# STM32F103ZE.net
KiCad netlist of a schematic drawn in Altium Designer
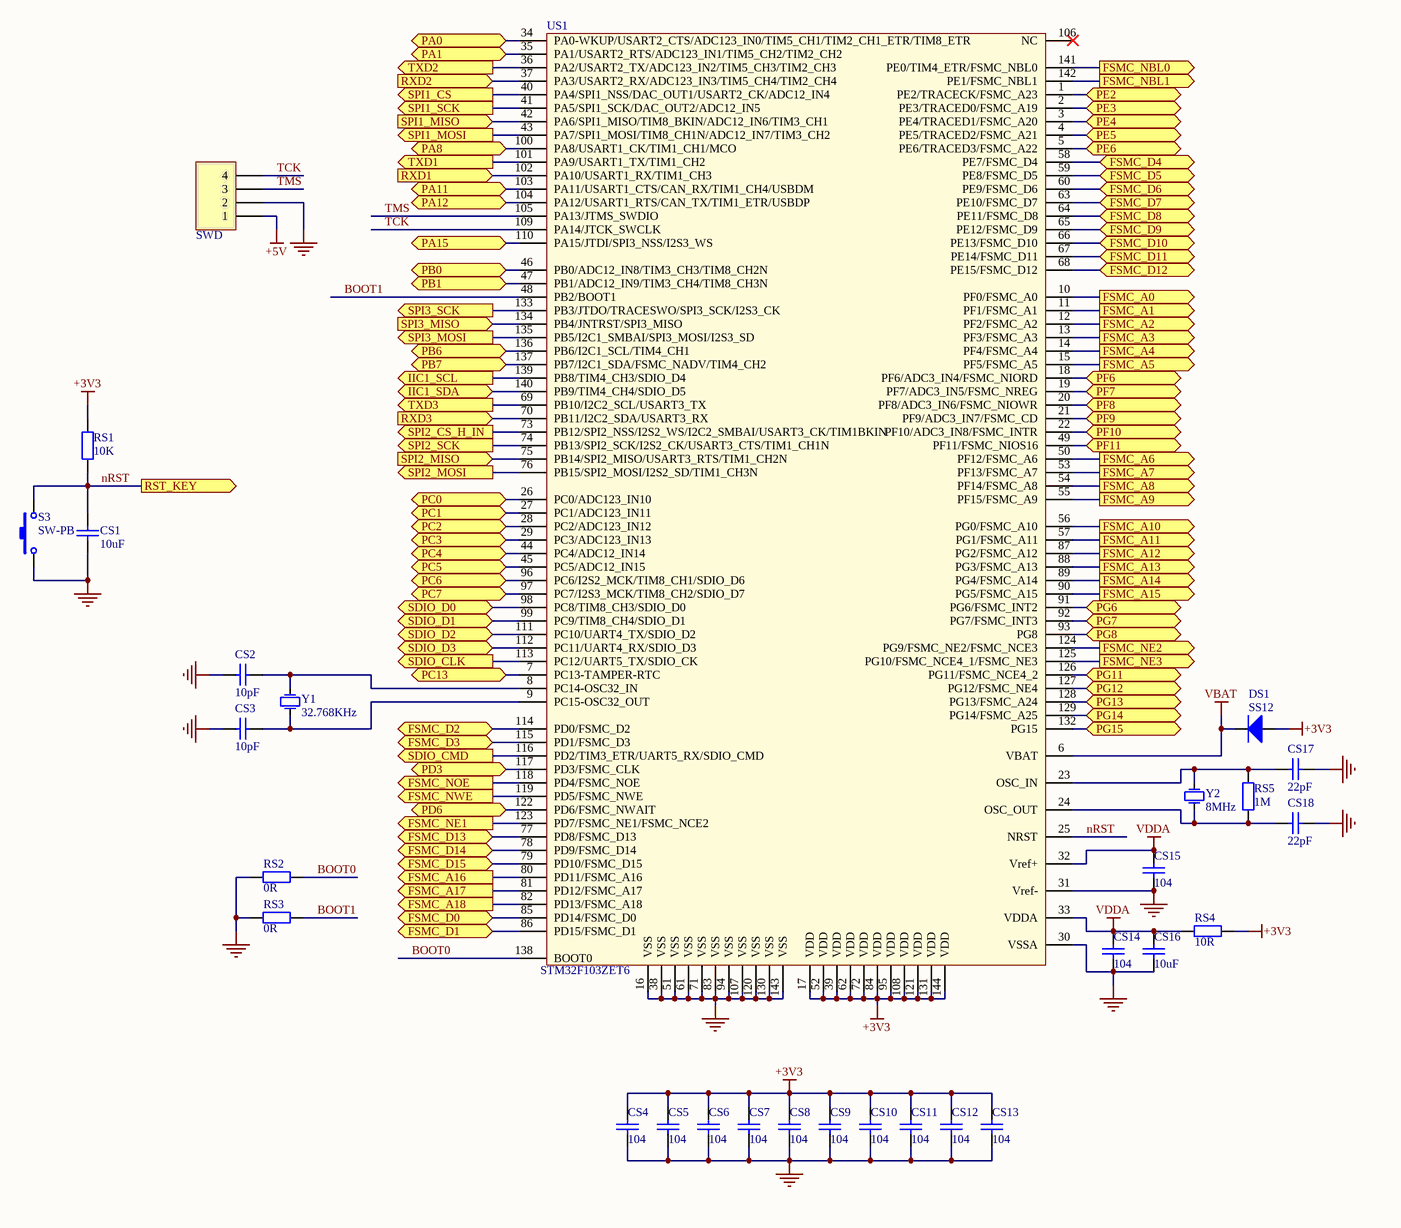
[diagram p0: STM32F103ZE.SchDoc]

(export (version "E")
  (design (tool "Eeschema 10.0.6"))
  (components
    (comp (ref "CS1")
      (value "10uF")
      (footprint "CAPC1608N")
      (description "Capacitor")
      (fields (field (name "Comment") "Cap1") (field (name "PUBLISHER") "Altium Limited"))
      (libsource (lib "Peace的集成库") (part "Cap1"))
    )
    (comp (ref "CS2")
      (value "10pF")
      (footprint "CAPC1608N")
      (description "Capacitor")
      (fields (field (name "Comment") "Cap1") (field (name "PUBLISHER") "Altium Limited"))
      (libsource (lib "Peace的集成库") (part "Cap1"))
    )
    (comp (ref "CS3")
      (value "10pF")
      (footprint "CAPC1608N")
      (description "Capacitor")
      (fields (field (name "Comment") "Cap1") (field (name "PUBLISHER") "Altium Limited"))
      (libsource (lib "Peace的集成库") (part "Cap1"))
    )
    (comp (ref "CS4")
      (value "104")
      (footprint "CAPC1608N")
      (description "Capacitor")
      (fields (field (name "Comment") "Cap1") (field (name "PUBLISHER") "Altium Limited"))
      (libsource (lib "Peace的集成库") (part "Cap1"))
    )
    (comp (ref "CS5")
      (value "104")
      (footprint "CAPC1608N")
      (description "Capacitor")
      (fields (field (name "Comment") "Cap1") (field (name "PUBLISHER") "Altium Limited"))
      (libsource (lib "Peace的集成库") (part "Cap1"))
    )
    (comp (ref "CS6")
      (value "104")
      (footprint "CAPC1608N")
      (description "Capacitor")
      (fields (field (name "Comment") "Cap1") (field (name "PUBLISHER") "Altium Limited"))
      (libsource (lib "Peace的集成库") (part "Cap1"))
    )
    (comp (ref "CS7")
      (value "104")
      (footprint "CAPC1608N")
      (description "Capacitor")
      (fields (field (name "Comment") "Cap1") (field (name "PUBLISHER") "Altium Limited"))
      (libsource (lib "Peace的集成库") (part "Cap1"))
    )
    (comp (ref "CS8")
      (value "104")
      (footprint "CAPC1608N")
      (description "Capacitor")
      (fields (field (name "Comment") "Cap1") (field (name "PUBLISHER") "Altium Limited"))
      (libsource (lib "Peace的集成库") (part "Cap1"))
    )
    (comp (ref "CS9")
      (value "104")
      (footprint "CAPC1608N")
      (description "Capacitor")
      (fields (field (name "Comment") "Cap1") (field (name "PUBLISHER") "Altium Limited"))
      (libsource (lib "Peace的集成库") (part "Cap1"))
    )
    (comp (ref "CS10")
      (value "104")
      (footprint "CAPC1608N")
      (description "Capacitor")
      (fields (field (name "Comment") "Cap1") (field (name "PUBLISHER") "Altium Limited"))
      (libsource (lib "Peace的集成库") (part "Cap1"))
    )
    (comp (ref "CS11")
      (value "104")
      (footprint "CAPC1608N")
      (description "Capacitor")
      (fields (field (name "Comment") "Cap1") (field (name "PUBLISHER") "Altium Limited"))
      (libsource (lib "Peace的集成库") (part "Cap1"))
    )
    (comp (ref "CS12")
      (value "104")
      (footprint "CAPC1608N")
      (description "Capacitor")
      (fields (field (name "Comment") "Cap1") (field (name "PUBLISHER") "Altium Limited"))
      (libsource (lib "Peace的集成库") (part "Cap1"))
    )
    (comp (ref "CS13")
      (value "104")
      (footprint "CAPC1608N")
      (description "Capacitor")
      (fields (field (name "Comment") "Cap1") (field (name "PUBLISHER") "Altium Limited"))
      (libsource (lib "Peace的集成库") (part "Cap1"))
    )
    (comp (ref "CS14")
      (value "104")
      (footprint "CAPC1608N")
      (description "Capacitor")
      (fields (field (name "Comment") "Cap1") (field (name "PUBLISHER") "Altium Limited"))
      (libsource (lib "Peace的集成库") (part "Cap1"))
    )
    (comp (ref "CS15")
      (value "104")
      (footprint "CAPC1608N")
      (description "Capacitor")
      (fields (field (name "Comment") "Cap1") (field (name "PUBLISHER") "Altium Limited"))
      (libsource (lib "Peace的集成库") (part "Cap1"))
    )
    (comp (ref "CS16")
      (value "10uF")
      (footprint "CAPC1608N")
      (description "Capacitor")
      (fields (field (name "Comment") "Cap1") (field (name "PUBLISHER") "Altium Limited"))
      (libsource (lib "Peace的集成库") (part "Cap1"))
    )
    (comp (ref "CS17")
      (value "22pF")
      (footprint "CAPC1608N")
      (description "Capacitor")
      (fields (field (name "Comment") "Cap1") (field (name "PUBLISHER") "Altium Limited"))
      (libsource (lib "Peace的集成库") (part "Cap1"))
    )
    (comp (ref "CS18")
      (value "22pF")
      (footprint "CAPC1608N")
      (description "Capacitor")
      (fields (field (name "Comment") "Cap1") (field (name "PUBLISHER") "Altium Limited"))
      (libsource (lib "Peace的集成库") (part "Cap1"))
    )
    (comp (ref "DS1")
      (value "Diode")
      (footprint "DO-214AC")
      (fields (field (name "SMA") "SS12"))
      (libsource (lib "Peace的集成库") (part "Diode"))
    )
    (comp (ref "RS1")
      (value "10K")
      (footprint "RESC1608N")
      (description "Resistor")
      (fields (field (name "Comment") "Res1") (field (name "PUBLISHER") "Altium Limited"))
      (libsource (lib "Peace的集成库") (part "Res1"))
    )
    (comp (ref "RS2")
      (value "0R")
      (footprint "RESC1608N")
      (description "Resistor")
      (fields (field (name "Comment") "Res1") (field (name "PUBLISHER") "Altium Limited"))
      (libsource (lib "") (part "Res1_1"))
    )
    (comp (ref "RS3")
      (value "0R")
      (footprint "RESC1608N")
      (description "Resistor")
      (fields (field (name "Comment") "Res1") (field (name "PUBLISHER") "Altium Limited"))
      (libsource (lib "") (part "Res1_1"))
    )
    (comp (ref "RS4")
      (value "10R")
      (footprint "RESC1608N")
      (description "Resistor")
      (fields (field (name "Comment") "Res1") (field (name "PUBLISHER") "Altium Limited"))
      (libsource (lib "") (part "Res1_1"))
    )
    (comp (ref "RS5")
      (value "1M")
      (footprint "RESC1608N")
      (description "Resistor")
      (fields (field (name "Comment") "Res1") (field (name "PUBLISHER") "Altium Limited"))
      (libsource (lib "Peace的集成库") (part "Res1"))
    )
    (comp (ref "S3")
      (value "SW-PB")
      (footprint "SW-3x6")
      (description "Switch")
      (fields (field (name "PUBLISHER") "Altium Limited"))
      (libsource (lib "Peace的集成库") (part "SW-PB"))
    )
    (comp (ref "SWD")
      (value "Header 4")
      (footprint "HDR1X4")
      (description "Header, 4-Pin")
      (fields (field (name "PUBLISHER") "Altium Limited"))
      (libsource (lib "Peace的集成库") (part "Header 4"))
    )
    (comp (ref "US1")
      (value "STM32F103ZET6")
      (footprint "LQFP144")
      (libsource (lib "Peace的集成库") (part "STM32F103ZET6"))
    )
    (comp (ref "Y1")
      (value "32.768KHz")
      (footprint "XTAL-206")
      (description "Crystal Oscillator")
      (fields (field (name "PUBLISHER") "Altium Limited"))
      (libsource (lib "Peace的集成库") (part "XTAL"))
    )
    (comp (ref "Y2")
      (value "8MHz")
      (footprint "49S")
      (description "Crystal Oscillator")
      (fields (field (name "PUBLISHER") "Altium Limited"))
      (libsource (lib "Peace的集成库") (part "XTAL"))
    )
  )
  (nets
    (net (code "1") (name "+3V3") (class "Default")
      (node (ref "CS10") (pin "2") (pinfunction "2_2") (pintype "passive"))
      (node (ref "CS11") (pin "2") (pinfunction "2_2") (pintype "passive"))
      (node (ref "CS12") (pin "2") (pinfunction "2_2") (pintype "passive"))
      (node (ref "CS13") (pin "2") (pinfunction "2_2") (pintype "passive"))
      (node (ref "CS4") (pin "2") (pinfunction "2_2") (pintype "passive"))
      (node (ref "CS5") (pin "2") (pinfunction "2_2") (pintype "passive"))
      (node (ref "CS6") (pin "2") (pinfunction "2_2") (pintype "passive"))
      (node (ref "CS7") (pin "2") (pinfunction "2_2") (pintype "passive"))
      (node (ref "CS8") (pin "2") (pinfunction "2_2") (pintype "passive"))
      (node (ref "CS9") (pin "2") (pinfunction "2_2") (pintype "passive"))
      (node (ref "DS1") (pin "1") (pinfunction "A_1") (pintype "passive"))
      (node (ref "RS1") (pin "2") (pinfunction "2_2") (pintype "passive"))
      (node (ref "RS4") (pin "2") (pinfunction "2_2") (pintype "passive"))
      (node (ref "US1") (pin "108") (pinfunction "VDD_108") (pintype "passive"))
      (node (ref "US1") (pin "121") (pinfunction "VDD_121") (pintype "passive"))
      (node (ref "US1") (pin "131") (pinfunction "VDD_131") (pintype "passive"))
      (node (ref "US1") (pin "144") (pinfunction "VDD_144") (pintype "passive"))
      (node (ref "US1") (pin "17") (pinfunction "VDD_17") (pintype "passive"))
      (node (ref "US1") (pin "39") (pinfunction "VDD_39") (pintype "passive"))
      (node (ref "US1") (pin "52") (pinfunction "VDD_52") (pintype "passive"))
      (node (ref "US1") (pin "62") (pinfunction "VDD_62") (pintype "passive"))
      (node (ref "US1") (pin "72") (pinfunction "VDD_72") (pintype "passive"))
      (node (ref "US1") (pin "84") (pinfunction "VDD_84") (pintype "passive"))
      (node (ref "US1") (pin "95") (pinfunction "VDD_95") (pintype "passive"))
    )
    (net (code "2") (name "+5V") (class "Default")
      (node (ref "SWD") (pin "1") (pinfunction "1_1") (pintype "passive"))
    )
    (net (code "3") (name "/BOOT0") (class "Default")
      (node (ref "RS2") (pin "2") (pinfunction "2_2") (pintype "passive"))
      (node (ref "US1") (pin "138") (pinfunction "BOOT0_138") (pintype "passive"))
    )
    (net (code "4") (name "/BOOT1") (class "Default")
      (node (ref "RS3") (pin "2") (pinfunction "2_2") (pintype "passive"))
      (node (ref "US1") (pin "48") (pinfunction "PB2/BOOT1_48") (pintype "passive"))
    )
    (net (code "5") (name "/FSMC_A0") (class "Default")
      (node (ref "US1") (pin "10") (pinfunction "PF0/FSMC_A0_10") (pintype "passive"))
    )
    (net (code "6") (name "/FSMC_A1") (class "Default")
      (node (ref "US1") (pin "11") (pinfunction "PF1/FSMC_A1_11") (pintype "passive"))
    )
    (net (code "7") (name "/FSMC_A2") (class "Default")
      (node (ref "US1") (pin "12") (pinfunction "PF2/FSMC_A2_12") (pintype "passive"))
    )
    (net (code "8") (name "/FSMC_A3") (class "Default")
      (node (ref "US1") (pin "13") (pinfunction "PF3/FSMC_A3_13") (pintype "passive"))
    )
    (net (code "9") (name "/FSMC_A4") (class "Default")
      (node (ref "US1") (pin "14") (pinfunction "PF4/FSMC_A4_14") (pintype "passive"))
    )
    (net (code "10") (name "/FSMC_A5") (class "Default")
      (node (ref "US1") (pin "15") (pinfunction "PF5/FSMC_A5_15") (pintype "passive"))
    )
    (net (code "11") (name "/FSMC_A6") (class "Default")
      (node (ref "US1") (pin "50") (pinfunction "PF12/FSMC_A6_50") (pintype "passive"))
    )
    (net (code "12") (name "/FSMC_A7") (class "Default")
      (node (ref "US1") (pin "53") (pinfunction "PF13/FSMC_A7_53") (pintype "passive"))
    )
    (net (code "13") (name "/FSMC_A8") (class "Default")
      (node (ref "US1") (pin "54") (pinfunction "PF14/FSMC_A8_54") (pintype "passive"))
    )
    (net (code "14") (name "/FSMC_A9") (class "Default")
      (node (ref "US1") (pin "55") (pinfunction "PF15/FSMC_A9_55") (pintype "passive"))
    )
    (net (code "15") (name "/FSMC_A10") (class "Default")
      (node (ref "US1") (pin "56") (pinfunction "PG0/FSMC_A10_56") (pintype "passive"))
    )
    (net (code "16") (name "/FSMC_A11") (class "Default")
      (node (ref "US1") (pin "57") (pinfunction "PG1/FSMC_A11_57") (pintype "passive"))
    )
    (net (code "17") (name "/FSMC_A12") (class "Default")
      (node (ref "US1") (pin "87") (pinfunction "PG2/FSMC_A12_87") (pintype "passive"))
    )
    (net (code "18") (name "/FSMC_A13") (class "Default")
      (node (ref "US1") (pin "88") (pinfunction "PG3/FSMC_A13_88") (pintype "passive"))
    )
    (net (code "19") (name "/FSMC_A14") (class "Default")
      (node (ref "US1") (pin "89") (pinfunction "PG4/FSMC_A14_89") (pintype "passive"))
    )
    (net (code "20") (name "/FSMC_A15") (class "Default")
      (node (ref "US1") (pin "90") (pinfunction "PG5/FSMC_A15_90") (pintype "passive"))
    )
    (net (code "21") (name "/FSMC_A16") (class "Default")
      (node (ref "US1") (pin "80") (pinfunction "PD11/FSMC_A16_80") (pintype "passive"))
    )
    (net (code "22") (name "/FSMC_A17") (class "Default")
      (node (ref "US1") (pin "81") (pinfunction "PD12/FSMC_A17_81") (pintype "passive"))
    )
    (net (code "23") (name "/FSMC_A18") (class "Default")
      (node (ref "US1") (pin "82") (pinfunction "PD13/FSMC_A18_82") (pintype "passive"))
    )
    (net (code "24") (name "/FSMC_D0") (class "Default")
      (node (ref "US1") (pin "85") (pinfunction "PD14/FSMC_D0_85") (pintype "passive"))
    )
    (net (code "25") (name "/FSMC_D1") (class "Default")
      (node (ref "US1") (pin "86") (pinfunction "PD15/FSMC_D1_86") (pintype "passive"))
    )
    (net (code "26") (name "/FSMC_D2") (class "Default")
      (node (ref "US1") (pin "114") (pinfunction "PD0/FSMC_D2_114") (pintype "passive"))
    )
    (net (code "27") (name "/FSMC_D3") (class "Default")
      (node (ref "US1") (pin "115") (pinfunction "PD1/FSMC_D3_115") (pintype "passive"))
    )
    (net (code "28") (name "/FSMC_D4") (class "Default")
      (node (ref "US1") (pin "58") (pinfunction "PE7/FSMC_D4_58") (pintype "passive"))
    )
    (net (code "29") (name "/FSMC_D5") (class "Default")
      (node (ref "US1") (pin "59") (pinfunction "PE8/FSMC_D5_59") (pintype "passive"))
    )
    (net (code "30") (name "/FSMC_D6") (class "Default")
      (node (ref "US1") (pin "60") (pinfunction "PE9/FSMC_D6_60") (pintype "passive"))
    )
    (net (code "31") (name "/FSMC_D7") (class "Default")
      (node (ref "US1") (pin "63") (pinfunction "PE10/FSMC_D7_63") (pintype "passive"))
    )
    (net (code "32") (name "/FSMC_D8") (class "Default")
      (node (ref "US1") (pin "64") (pinfunction "PE11/FSMC_D8_64") (pintype "passive"))
    )
    (net (code "33") (name "/FSMC_D9") (class "Default")
      (node (ref "US1") (pin "65") (pinfunction "PE12/FSMC_D9_65") (pintype "passive"))
    )
    (net (code "34") (name "/FSMC_D10") (class "Default")
      (node (ref "US1") (pin "66") (pinfunction "PE13/FSMC_D10_66") (pintype "passive"))
    )
    (net (code "35") (name "/FSMC_D11") (class "Default")
      (node (ref "US1") (pin "67") (pinfunction "PE14/FSMC_D11_67") (pintype "passive"))
    )
    (net (code "36") (name "/FSMC_D12") (class "Default")
      (node (ref "US1") (pin "68") (pinfunction "PE15/FSMC_D12_68") (pintype "passive"))
    )
    (net (code "37") (name "/FSMC_D13") (class "Default")
      (node (ref "US1") (pin "77") (pinfunction "PD8/FSMC_D13_77") (pintype "passive"))
    )
    (net (code "38") (name "/FSMC_D14") (class "Default")
      (node (ref "US1") (pin "78") (pinfunction "PD9/FSMC_D14_78") (pintype "passive"))
    )
    (net (code "39") (name "/FSMC_D15") (class "Default")
      (node (ref "US1") (pin "79") (pinfunction "PD10/FSMC_D15_79") (pintype "passive"))
    )
    (net (code "40") (name "/FSMC_NBL0") (class "Default")
      (node (ref "US1") (pin "141") (pinfunction "PE0/TIM4_ETR/FSMC_NBL0_141") (pintype "passive"))
    )
    (net (code "41") (name "/FSMC_NBL1") (class "Default")
      (node (ref "US1") (pin "142") (pinfunction "PE1/FSMC_NBL1_142") (pintype "passive"))
    )
    (net (code "42") (name "/FSMC_NE1") (class "Default")
      (node (ref "US1") (pin "123") (pinfunction "PD7/FSMC_NE1/FSMC_NCE2_123") (pintype "passive"))
    )
    (net (code "43") (name "/FSMC_NE2") (class "Default")
      (node (ref "US1") (pin "124") (pinfunction "PG9/FSMC_NE2/FSMC_NCE3_124") (pintype "passive"))
    )
    (net (code "44") (name "/FSMC_NE3") (class "Default")
      (node (ref "US1") (pin "125") (pinfunction "PG10/FSMC_NCE4_1/FSMC_NE3_125") (pintype "passive"))
    )
    (net (code "45") (name "/FSMC_NOE") (class "Default")
      (node (ref "US1") (pin "118") (pinfunction "PD4/FSMC_NOE_118") (pintype "passive"))
    )
    (net (code "46") (name "/FSMC_NWE") (class "Default")
      (node (ref "US1") (pin "119") (pinfunction "PD5/FSMC_NWE_119") (pintype "passive"))
    )
    (net (code "47") (name "/IIC1_SCL") (class "Default")
      (node (ref "US1") (pin "139") (pinfunction "PB8/TIM4_CH3/SDIO_D4_139") (pintype "passive"))
    )
    (net (code "48") (name "/IIC1_SDA") (class "Default")
      (node (ref "US1") (pin "140") (pinfunction "PB9/TIM4_CH4/SDIO_D5_140") (pintype "passive"))
    )
    (net (code "49") (name "/PA0") (class "Default")
      (node (ref "US1") (pin "34") (pinfunction "PA0-WKUP/USART2_CTS/ADC123_IN0/TIM5_CH1/TIM2_CH1_ETR/TIM8_ETR_34") (pintype "passive"))
    )
    (net (code "50") (name "/PA1") (class "Default")
      (node (ref "US1") (pin "35") (pinfunction "PA1/USART2_RTS/ADC123_IN1/TIM5_CH2/TIM2_CH2_35") (pintype "passive"))
    )
    (net (code "51") (name "/PA8") (class "Default")
      (node (ref "US1") (pin "100") (pinfunction "PA8/USART1_CK/TIM1_CH1/MCO_100") (pintype "passive"))
    )
    (net (code "52") (name "/PA11") (class "Default")
      (node (ref "US1") (pin "103") (pinfunction "PA11/USART1_CTS/CAN_RX/TIM1_CH4/USBDM_103") (pintype "passive"))
    )
    (net (code "53") (name "/PA12") (class "Default")
      (node (ref "US1") (pin "104") (pinfunction "PA12/USART1_RTS/CAN_TX/TIM1_ETR/USBDP_104") (pintype "passive"))
    )
    (net (code "54") (name "/PA15") (class "Default")
      (node (ref "US1") (pin "110") (pinfunction "PA15/JTDI/SPI3_NSS/I2S3_WS_110") (pintype "passive"))
    )
    (net (code "55") (name "/PB0") (class "Default")
      (node (ref "US1") (pin "46") (pinfunction "PB0/ADC12_IN8/TIM3_CH3/TIM8_CH2N_46") (pintype "passive"))
    )
    (net (code "56") (name "/PB1") (class "Default")
      (node (ref "US1") (pin "47") (pinfunction "PB1/ADC12_IN9/TIM3_CH4/TIM8_CH3N_47") (pintype "passive"))
    )
    (net (code "57") (name "/PB6") (class "Default")
      (node (ref "US1") (pin "136") (pinfunction "PB6/I2C1_SCL/TIM4_CH1_136") (pintype "passive"))
    )
    (net (code "58") (name "/PB7") (class "Default")
      (node (ref "US1") (pin "137") (pinfunction "PB7/I2C1_SDA/FSMC_NADV/TIM4_CH2_137") (pintype "passive"))
    )
    (net (code "59") (name "/PC0") (class "Default")
      (node (ref "US1") (pin "26") (pinfunction "PC0/ADC123_IN10_26") (pintype "passive"))
    )
    (net (code "60") (name "/PC1") (class "Default")
      (node (ref "US1") (pin "27") (pinfunction "PC1/ADC123_IN11_27") (pintype "passive"))
    )
    (net (code "61") (name "/PC2") (class "Default")
      (node (ref "US1") (pin "28") (pinfunction "PC2/ADC123_IN12_28") (pintype "passive"))
    )
    (net (code "62") (name "/PC3") (class "Default")
      (node (ref "US1") (pin "29") (pinfunction "PC3/ADC123_IN13_29") (pintype "passive"))
    )
    (net (code "63") (name "/PC4") (class "Default")
      (node (ref "US1") (pin "44") (pinfunction "PC4/ADC12_IN14_44") (pintype "passive"))
    )
    (net (code "64") (name "/PC5") (class "Default")
      (node (ref "US1") (pin "45") (pinfunction "PC5/ADC12_IN15_45") (pintype "passive"))
    )
    (net (code "65") (name "/PC6") (class "Default")
      (node (ref "US1") (pin "96") (pinfunction "PC6/I2S2_MCK/TIM8_CH1/SDIO_D6_96") (pintype "passive"))
    )
    (net (code "66") (name "/PC7") (class "Default")
      (node (ref "US1") (pin "97") (pinfunction "PC7/I2S3_MCK/TIM8_CH2/SDIO_D7_97") (pintype "passive"))
    )
    (net (code "67") (name "/PC13") (class "Default")
      (node (ref "US1") (pin "7") (pinfunction "PC13-TAMPER-RTC_7") (pintype "passive"))
    )
    (net (code "68") (name "/PD3") (class "Default")
      (node (ref "US1") (pin "117") (pinfunction "PD3/FSMC_CLK_117") (pintype "passive"))
    )
    (net (code "69") (name "/PD6") (class "Default")
      (node (ref "US1") (pin "122") (pinfunction "PD6/FSMC_NWAIT_122") (pintype "passive"))
    )
    (net (code "70") (name "/PE2") (class "Default")
      (node (ref "US1") (pin "1") (pinfunction "PE2/TRACECK/FSMC_A23_1") (pintype "passive"))
    )
    (net (code "71") (name "/PE3") (class "Default")
      (node (ref "US1") (pin "2") (pinfunction "PE3/TRACED0/FSMC_A19_2") (pintype "passive"))
    )
    (net (code "72") (name "/PE4") (class "Default")
      (node (ref "US1") (pin "3") (pinfunction "PE4/TRACED1/FSMC_A20_3") (pintype "passive"))
    )
    (net (code "73") (name "/PE5") (class "Default")
      (node (ref "US1") (pin "4") (pinfunction "PE5/TRACED2/FSMC_A21_4") (pintype "passive"))
    )
    (net (code "74") (name "/PE6") (class "Default")
      (node (ref "US1") (pin "5") (pinfunction "PE6/TRACED3/FSMC_A22_5") (pintype "passive"))
    )
    (net (code "75") (name "/PF6") (class "Default")
      (node (ref "US1") (pin "18") (pinfunction "PF6/ADC3_IN4/FSMC_NIORD_18") (pintype "passive"))
    )
    (net (code "76") (name "/PF7") (class "Default")
      (node (ref "US1") (pin "19") (pinfunction "PF7/ADC3_IN5/FSMC_NREG_19") (pintype "passive"))
    )
    (net (code "77") (name "/PF8") (class "Default")
      (node (ref "US1") (pin "20") (pinfunction "PF8/ADC3_IN6/FSMC_NIOWR_20") (pintype "passive"))
    )
    (net (code "78") (name "/PF9") (class "Default")
      (node (ref "US1") (pin "21") (pinfunction "PF9/ADC3_IN7/FSMC_CD_21") (pintype "passive"))
    )
    (net (code "79") (name "/PF10") (class "Default")
      (node (ref "US1") (pin "22") (pinfunction "PF10/ADC3_IN8/FSMC_INTR_22") (pintype "passive"))
    )
    (net (code "80") (name "/PF11") (class "Default")
      (node (ref "US1") (pin "49") (pinfunction "PF11/FSMC_NIOS16_49") (pintype "passive"))
    )
    (net (code "81") (name "/PG6") (class "Default")
      (node (ref "US1") (pin "91") (pinfunction "PG6/FSMC_INT2_91") (pintype "passive"))
    )
    (net (code "82") (name "/PG7") (class "Default")
      (node (ref "US1") (pin "92") (pinfunction "PG7/FSMC_INT3_92") (pintype "passive"))
    )
    (net (code "83") (name "/PG8") (class "Default")
      (node (ref "US1") (pin "93") (pinfunction "PG8_93") (pintype "passive"))
    )
    (net (code "84") (name "/PG11") (class "Default")
      (node (ref "US1") (pin "126") (pinfunction "PG11/FSMC_NCE4_2_126") (pintype "passive"))
    )
    (net (code "85") (name "/PG12") (class "Default")
      (node (ref "US1") (pin "127") (pinfunction "PG12/FSMC_NE4_127") (pintype "passive"))
    )
    (net (code "86") (name "/PG13") (class "Default")
      (node (ref "US1") (pin "128") (pinfunction "PG13/FSMC_A24_128") (pintype "passive"))
    )
    (net (code "87") (name "/PG14") (class "Default")
      (node (ref "US1") (pin "129") (pinfunction "PG14/FSMC_A25_129") (pintype "passive"))
    )
    (net (code "88") (name "/PG15") (class "Default")
      (node (ref "US1") (pin "132") (pinfunction "PG15_132") (pintype "passive"))
    )
    (net (code "89") (name "/RXD1") (class "Default")
      (node (ref "US1") (pin "102") (pinfunction "PA10/USART1_RX/TIM1_CH3_102") (pintype "passive"))
    )
    (net (code "90") (name "/RXD2") (class "Default")
      (node (ref "US1") (pin "37") (pinfunction "PA3/USART2_RX/ADC123_IN3/TIM5_CH4/TIM2_CH4_37") (pintype "passive"))
    )
    (net (code "91") (name "/RXD3") (class "Default")
      (node (ref "US1") (pin "70") (pinfunction "PB11/I2C2_SDA/USART3_RX_70") (pintype "passive"))
    )
    (net (code "92") (name "/SDIO_CLK") (class "Default")
      (node (ref "US1") (pin "113") (pinfunction "PC12/UART5_TX/SDIO_CK_113") (pintype "passive"))
    )
    (net (code "93") (name "/SDIO_CMD") (class "Default")
      (node (ref "US1") (pin "116") (pinfunction "PD2/TIM3_ETR/UART5_RX/SDIO_CMD_116") (pintype "passive"))
    )
    (net (code "94") (name "/SDIO_D0") (class "Default")
      (node (ref "US1") (pin "98") (pinfunction "PC8/TIM8_CH3/SDIO_D0_98") (pintype "passive"))
    )
    (net (code "95") (name "/SDIO_D1") (class "Default")
      (node (ref "US1") (pin "99") (pinfunction "PC9/TIM8_CH4/SDIO_D1_99") (pintype "passive"))
    )
    (net (code "96") (name "/SDIO_D2") (class "Default")
      (node (ref "US1") (pin "111") (pinfunction "PC10/UART4_TX/SDIO_D2_111") (pintype "passive"))
    )
    (net (code "97") (name "/SDIO_D3") (class "Default")
      (node (ref "US1") (pin "112") (pinfunction "PC11/UART4_RX/SDIO_D3_112") (pintype "passive"))
    )
    (net (code "98") (name "/SPI1_CS") (class "Default")
      (node (ref "US1") (pin "40") (pinfunction "PA4/SPI1_NSS/DAC_OUT1/USART2_CK/ADC12_IN4_40") (pintype "passive"))
    )
    (net (code "99") (name "/SPI1_MISO") (class "Default")
      (node (ref "US1") (pin "42") (pinfunction "PA6/SPI1_MISO/TIM8_BKIN/ADC12_IN6/TIM3_CH1_42") (pintype "passive"))
    )
    (net (code "100") (name "/SPI1_MOSI") (class "Default")
      (node (ref "US1") (pin "43") (pinfunction "PA7/SPI1_MOSI/TIM8_CH1N/ADC12_IN7/TIM3_CH2_43") (pintype "passive"))
    )
    (net (code "101") (name "/SPI1_SCK") (class "Default")
      (node (ref "US1") (pin "41") (pinfunction "PA5/SPI1_SCK/DAC_OUT2/ADC12_IN5_41") (pintype "passive"))
    )
    (net (code "102") (name "/SPI2_CS_H_IN") (class "Default")
      (node (ref "US1") (pin "73") (pinfunction "PB12/SPI2_NSS/I2S2_WS/I2C2_SMBAI/USART3_CK/TIM1BKIN_73") (pintype "passive"))
    )
    (net (code "103") (name "/SPI2_MISO") (class "Default")
      (node (ref "US1") (pin "75") (pinfunction "PB14/SPI2_MISO/USART3_RTS/TIM1_CH2N_75") (pintype "passive"))
    )
    (net (code "104") (name "/SPI2_MOSI") (class "Default")
      (node (ref "US1") (pin "76") (pinfunction "PB15/SPI2_MOSI/I2S2_SD/TIM1_CH3N_76") (pintype "passive"))
    )
    (net (code "105") (name "/SPI2_SCK") (class "Default")
      (node (ref "US1") (pin "74") (pinfunction "PB13/SPI2_SCK/I2S2_CK/USART3_CTS/TIM1_CH1N_74") (pintype "passive"))
    )
    (net (code "106") (name "/SPI3_MISO") (class "Default")
      (node (ref "US1") (pin "134") (pinfunction "PB4/JNTRST/SPI3_MISO_134") (pintype "passive"))
    )
    (net (code "107") (name "/SPI3_MOSI") (class "Default")
      (node (ref "US1") (pin "135") (pinfunction "PB5/I2C1_SMBAI/SPI3_MOSI/I2S3_SD_135") (pintype "passive"))
    )
    (net (code "108") (name "/SPI3_SCK") (class "Default")
      (node (ref "US1") (pin "133") (pinfunction "PB3/JTDO/TRACESWO/SPI3_SCK/I2S3_CK_133") (pintype "passive"))
    )
    (net (code "109") (name "/TCK") (class "Default")
      (node (ref "SWD") (pin "4") (pinfunction "4_4") (pintype "passive"))
      (node (ref "US1") (pin "109") (pinfunction "PA14/JTCK_SWCLK_109") (pintype "passive"))
    )
    (net (code "110") (name "/TMS") (class "Default")
      (node (ref "SWD") (pin "3") (pinfunction "3_3") (pintype "passive"))
      (node (ref "US1") (pin "105") (pinfunction "PA13/JTMS_SWDIO_105") (pintype "passive"))
    )
    (net (code "111") (name "/TXD1") (class "Default")
      (node (ref "US1") (pin "101") (pinfunction "PA9/USART1_TX/TIM1_CH2_101") (pintype "passive"))
    )
    (net (code "112") (name "/TXD2") (class "Default")
      (node (ref "US1") (pin "36") (pinfunction "PA2/USART2_TX/ADC123_IN2/TIM5_CH3/TIM2_CH3_36") (pintype "passive"))
    )
    (net (code "113") (name "/TXD3") (class "Default")
      (node (ref "US1") (pin "69") (pinfunction "PB10/I2C2_SCL/USART3_TX_69") (pintype "passive"))
    )
    (net (code "114") (name "/nRST") (class "Default")
      (node (ref "CS1") (pin "2") (pinfunction "2_2") (pintype "passive"))
      (node (ref "RS1") (pin "1") (pinfunction "1_1") (pintype "passive"))
      (node (ref "S3") (pin "2") (pinfunction "2_2") (pintype "passive"))
      (node (ref "US1") (pin "25") (pinfunction "NRST_25") (pintype "passive"))
    )
    (net (code "115") (name "GND") (class "Default")
      (node (ref "CS1") (pin "1") (pinfunction "1_1") (pintype "passive"))
      (node (ref "CS10") (pin "1") (pinfunction "1_1") (pintype "passive"))
      (node (ref "CS11") (pin "1") (pinfunction "1_1") (pintype "passive"))
      (node (ref "CS12") (pin "1") (pinfunction "1_1") (pintype "passive"))
      (node (ref "CS13") (pin "1") (pinfunction "1_1") (pintype "passive"))
      (node (ref "CS14") (pin "1") (pinfunction "1_1") (pintype "passive"))
      (node (ref "CS15") (pin "1") (pinfunction "1_1") (pintype "passive"))
      (node (ref "CS16") (pin "1") (pinfunction "1_1") (pintype "passive"))
      (node (ref "CS17") (pin "1") (pinfunction "1_1") (pintype "passive"))
      (node (ref "CS18") (pin "1") (pinfunction "1_1") (pintype "passive"))
      (node (ref "CS2") (pin "1") (pinfunction "1_1") (pintype "passive"))
      (node (ref "CS3") (pin "1") (pinfunction "1_1") (pintype "passive"))
      (node (ref "CS4") (pin "1") (pinfunction "1_1") (pintype "passive"))
      (node (ref "CS5") (pin "1") (pinfunction "1_1") (pintype "passive"))
      (node (ref "CS6") (pin "1") (pinfunction "1_1") (pintype "passive"))
      (node (ref "CS7") (pin "1") (pinfunction "1_1") (pintype "passive"))
      (node (ref "CS8") (pin "1") (pinfunction "1_1") (pintype "passive"))
      (node (ref "CS9") (pin "1") (pinfunction "1_1") (pintype "passive"))
      (node (ref "RS2") (pin "1") (pinfunction "1_1") (pintype "passive"))
      (node (ref "RS3") (pin "1") (pinfunction "1_1") (pintype "passive"))
      (node (ref "S3") (pin "1") (pinfunction "1_1") (pintype "passive"))
      (node (ref "SWD") (pin "2") (pinfunction "2_2") (pintype "passive"))
      (node (ref "US1") (pin "107") (pinfunction "VSS_107") (pintype "passive"))
      (node (ref "US1") (pin "120") (pinfunction "VSS_120") (pintype "passive"))
      (node (ref "US1") (pin "130") (pinfunction "VSS_130") (pintype "passive"))
      (node (ref "US1") (pin "143") (pinfunction "VSS_143") (pintype "passive"))
      (node (ref "US1") (pin "16") (pinfunction "VSS_16") (pintype "passive"))
      (node (ref "US1") (pin "30") (pinfunction "VSSA_30") (pintype "passive"))
      (node (ref "US1") (pin "31") (pinfunction "Vref-_31") (pintype "passive"))
      (node (ref "US1") (pin "38") (pinfunction "VSS_38") (pintype "passive"))
      (node (ref "US1") (pin "51") (pinfunction "VSS_51") (pintype "passive"))
      (node (ref "US1") (pin "61") (pinfunction "VSS_61") (pintype "passive"))
      (node (ref "US1") (pin "71") (pinfunction "VSS_71") (pintype "passive"))
      (node (ref "US1") (pin "83") (pinfunction "VSS_83") (pintype "passive"))
      (node (ref "US1") (pin "94") (pinfunction "VSS_94") (pintype "passive"))
    )
    (net (code "116") (name "Net-(US1-OSC_IN)") (class "Default")
      (node (ref "CS17") (pin "2") (pinfunction "2_2") (pintype "passive"))
      (node (ref "RS5") (pin "2") (pinfunction "2_2") (pintype "passive"))
      (node (ref "US1") (pin "23") (pinfunction "OSC_IN_23") (pintype "passive"))
      (node (ref "Y2") (pin "2") (pinfunction "OSC2_2") (pintype "passive"))
    )
    (net (code "117") (name "Net-(US1-OSC_OUT)") (class "Default")
      (node (ref "CS18") (pin "2") (pinfunction "2_2") (pintype "passive"))
      (node (ref "RS5") (pin "1") (pinfunction "1_1") (pintype "passive"))
      (node (ref "US1") (pin "24") (pinfunction "OSC_OUT_24") (pintype "passive"))
      (node (ref "Y2") (pin "1") (pinfunction "OSC1_1") (pintype "passive"))
    )
    (net (code "118") (name "Net-(US1-PC14-OSC32_IN)") (class "Default")
      (node (ref "CS2") (pin "2") (pinfunction "2_2") (pintype "passive"))
      (node (ref "US1") (pin "8") (pinfunction "PC14-OSC32_IN_8") (pintype "passive"))
      (node (ref "Y1") (pin "2") (pinfunction "OSC2_2") (pintype "passive"))
    )
    (net (code "119") (name "Net-(US1-PC15-OSC32_OUT)") (class "Default")
      (node (ref "CS3") (pin "2") (pinfunction "2_2") (pintype "passive"))
      (node (ref "US1") (pin "9") (pinfunction "PC15-OSC32_OUT_9") (pintype "passive"))
      (node (ref "Y1") (pin "1") (pinfunction "OSC1_1") (pintype "passive"))
    )
    (net (code "120") (name "VBAT") (class "Default")
      (node (ref "DS1") (pin "2") (pinfunction "K_2") (pintype "passive"))
      (node (ref "US1") (pin "6") (pinfunction "VBAT_6") (pintype "passive"))
    )
    (net (code "121") (name "VDDA") (class "Default")
      (node (ref "CS14") (pin "2") (pinfunction "2_2") (pintype "passive"))
      (node (ref "CS15") (pin "2") (pinfunction "2_2") (pintype "passive"))
      (node (ref "CS16") (pin "2") (pinfunction "2_2") (pintype "passive"))
      (node (ref "RS4") (pin "1") (pinfunction "1_1") (pintype "passive"))
      (node (ref "US1") (pin "32") (pinfunction "Vref+_32") (pintype "passive"))
      (node (ref "US1") (pin "33") (pinfunction "VDDA_33") (pintype "passive"))
    )
    (net (code "122") (name "unconnected-(US1-NC-Pad106)") (class "Default")
      (node (ref "US1") (pin "106") (pinfunction "NC_106") (pintype "passive+no_connect"))
    )
  )
)
